# Sheet1.net
KiCad netlist of a schematic drawn in Altium Designer
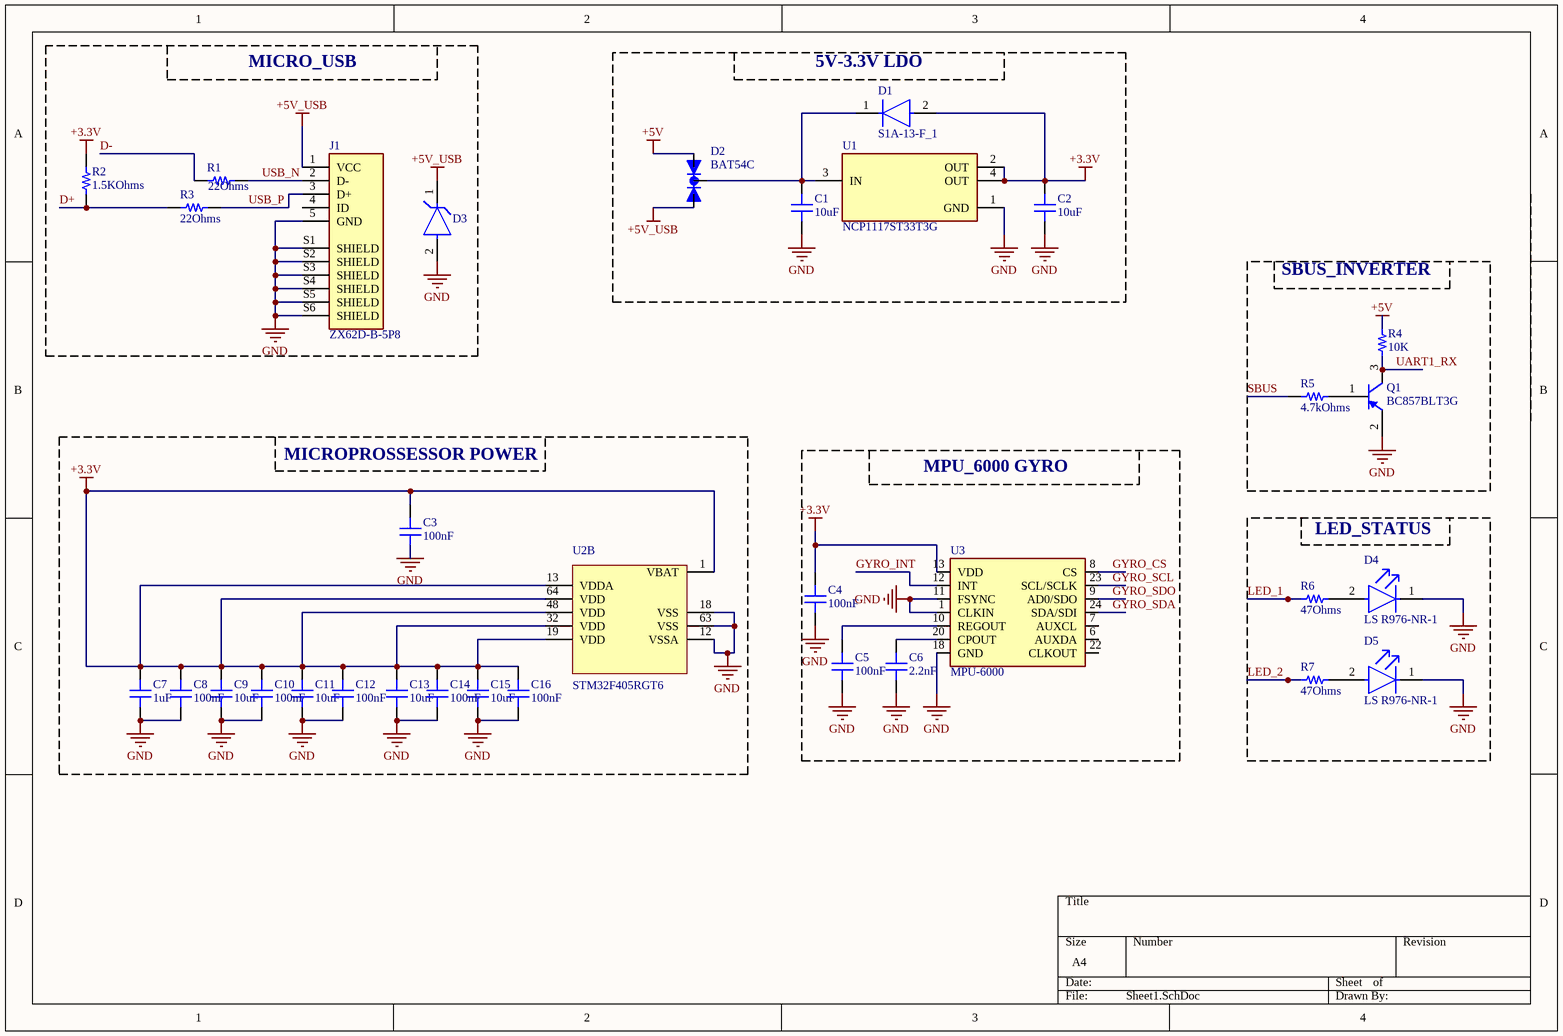
[diagram p0: Sheet1.SchDoc]

(export (version "E")
  (design (tool "Eeschema 10.0.6"))
  (components
    (comp (ref "C1")
      (value "10uF")
      (footprint "CAP-0603")
      (description "10 µF ±20% 16V Ceramic Capacitor X5R 0603 (1608 Metric)")
      (fields
        (field (name "MANUFACTURER") "KEMET")
        (field (name "MANUFACTURER PART NUMBER") "C0603C104K5RAC7411")
      )
      (libsource (lib "Schlib1") (part "CC0603MRX5R7BB106"))
    )
    (comp (ref "C2")
      (value "10uF")
      (footprint "CAP-0603")
      (description "10 µF ±20% 16V Ceramic Capacitor X5R 0603 (1608 Metric)")
      (fields
        (field (name "MANUFACTURER") "KEMET")
        (field (name "MANUFACTURER PART NUMBER") "C0603C104K5RAC7411")
      )
      (libsource (lib "Schlib1") (part "CC0603MRX5R7BB106"))
    )
    (comp (ref "C3")
      (value "100nF")
      (footprint "CAP-0603")
      (description "Cap Ceramic 0.1uF 50V X7R 10% SMD 0603 125°C Paper T/R 100nF")
      (fields
        (field (name "MANUFACTURER") "KEMET")
        (field (name "MANUFACTURER PART NUMBER") "C0603C104K5RAC7411")
      )
      (libsource (lib "Schlib1") (part "C0603C104K5RAC7411"))
    )
    (comp (ref "C4")
      (value "100nF")
      (footprint "CAP-0603")
      (description "Cap Ceramic 0.1uF 50V X7R 10% SMD 0603 125°C Paper T/R 100nF")
      (fields
        (field (name "MANUFACTURER") "KEMET")
        (field (name "MANUFACTURER PART NUMBER") "C0603C104K5RAC7411")
      )
      (libsource (lib "Schlib1") (part "C0603C104K5RAC7411"))
    )
    (comp (ref "C5")
      (value "100nF")
      (footprint "CAP-0603")
      (description "Cap Ceramic 0.1uF 50V X7R 10% SMD 0603 125°C Paper T/R 100nF")
      (fields
        (field (name "MANUFACTURER") "KEMET")
        (field (name "MANUFACTURER PART NUMBER") "C0603C104K5RAC7411")
      )
      (libsource (lib "Schlib1") (part "C0603C104K5RAC7411"))
    )
    (comp (ref "C6")
      (value "2.2nF")
      (footprint "CAP-0603")
      (description "2200 pF ±10% 16V Ceramic Capacitor X7R 0603 (1608 Metric) 2.2nF")
      (fields
        (field (name "MANUFACTURER") "KEMET")
        (field (name "MANUFACTURER PART NUMBER") "C0603C104K5RAC7411")
      )
      (libsource (lib "Schlib1") (part "0603YC222KAT2A"))
    )
    (comp (ref "C7")
      (value "1uF")
      (footprint "CAP-0603")
      (description "Cap Ceramic 1uF 16V X5R 20% Pad SMD 0603 85C Automotive T/R")
      (fields
        (field (name "MANUFACTURER") "KEMET")
        (field (name "MANUFACTURER PART NUMBER") "C0603C104K5RAC7411")
      )
      (libsource (lib "Schlib1") (part "CC0603MRX5R7BB105"))
    )
    (comp (ref "C8")
      (value "100nF")
      (footprint "CAP-0603")
      (description "Cap Ceramic 0.1uF 50V X7R 10% SMD 0603 125°C Paper T/R 100nF")
      (fields
        (field (name "MANUFACTURER") "KEMET")
        (field (name "MANUFACTURER PART NUMBER") "C0603C104K5RAC7411")
      )
      (libsource (lib "Schlib1") (part "C0603C104K5RAC7411"))
    )
    (comp (ref "C9")
      (value "10uF")
      (footprint "CAP-0603")
      (description "10 µF ±20% 16V Ceramic Capacitor X5R 0603 (1608 Metric)")
      (fields
        (field (name "MANUFACTURER") "KEMET")
        (field (name "MANUFACTURER PART NUMBER") "C0603C104K5RAC7411")
      )
      (libsource (lib "Schlib1") (part "CC0603MRX5R7BB106"))
    )
    (comp (ref "C10")
      (value "100nF")
      (footprint "CAP-0603")
      (description "Cap Ceramic 0.1uF 50V X7R 10% SMD 0603 125°C Paper T/R 100nF")
      (fields
        (field (name "MANUFACTURER") "KEMET")
        (field (name "MANUFACTURER PART NUMBER") "C0603C104K5RAC7411")
      )
      (libsource (lib "Schlib1") (part "C0603C104K5RAC7411"))
    )
    (comp (ref "C11")
      (value "10uF")
      (footprint "CAP-0603")
      (description "10 µF ±20% 16V Ceramic Capacitor X5R 0603 (1608 Metric)")
      (fields
        (field (name "MANUFACTURER") "KEMET")
        (field (name "MANUFACTURER PART NUMBER") "C0603C104K5RAC7411")
      )
      (libsource (lib "Schlib1") (part "CC0603MRX5R7BB106"))
    )
    (comp (ref "C12")
      (value "100nF")
      (footprint "CAP-0603")
      (description "Cap Ceramic 0.1uF 50V X7R 10% SMD 0603 125°C Paper T/R 100nF")
      (fields
        (field (name "MANUFACTURER") "KEMET")
        (field (name "MANUFACTURER PART NUMBER") "C0603C104K5RAC7411")
      )
      (libsource (lib "Schlib1") (part "C0603C104K5RAC7411"))
    )
    (comp (ref "C13")
      (value "10uF")
      (footprint "CAP-0603")
      (description "10 µF ±20% 16V Ceramic Capacitor X5R 0603 (1608 Metric)")
      (fields
        (field (name "MANUFACTURER") "KEMET")
        (field (name "MANUFACTURER PART NUMBER") "C0603C104K5RAC7411")
      )
      (libsource (lib "Schlib1") (part "CC0603MRX5R7BB106"))
    )
    (comp (ref "C14")
      (value "100nF")
      (footprint "CAP-0603")
      (description "Cap Ceramic 0.1uF 50V X7R 10% SMD 0603 125°C Paper T/R 100nF")
      (fields
        (field (name "MANUFACTURER") "KEMET")
        (field (name "MANUFACTURER PART NUMBER") "C0603C104K5RAC7411")
      )
      (libsource (lib "Schlib1") (part "C0603C104K5RAC7411"))
    )
    (comp (ref "C15")
      (value "10uF")
      (footprint "CAP-0603")
      (description "10 µF ±20% 16V Ceramic Capacitor X5R 0603 (1608 Metric)")
      (fields
        (field (name "MANUFACTURER") "KEMET")
        (field (name "MANUFACTURER PART NUMBER") "C0603C104K5RAC7411")
      )
      (libsource (lib "Schlib1") (part "CC0603MRX5R7BB106"))
    )
    (comp (ref "C16")
      (value "100nF")
      (footprint "CAP-0603")
      (description "Cap Ceramic 0.1uF 50V X7R 10% SMD 0603 125°C Paper T/R 100nF")
      (fields
        (field (name "MANUFACTURER") "KEMET")
        (field (name "MANUFACTURER PART NUMBER") "C0603C104K5RAC7411")
      )
      (libsource (lib "Schlib1") (part "C0603C104K5RAC7411"))
    )
    (comp (ref "D1")
      (value "S1A-13-F_1")
      (footprint "S1A-13-F")
      (description "VR=50V IF=1A 10pF Trr=3us")
      (fields (field (name "MANUFACTURER") "Diodes") (field (name "MANUFACTURER PART NUMBER") "S1A-13-F"))
      (libsource (lib "Schlib1") (part "S1A-13-F_1"))
    )
    (comp (ref "D2")
      (value "BAT54C")
      (footprint "SOT23-3")
      (description "Diode Array 1 Pair Common Cathode Schottky 30V 200mA Surface Mount TO-236-3, SC-59, SOT-23-3")
      (fields (field (name "MF") "ON Semiconductor"))
      (libsource (lib "Schlib1") (part "BAT54C"))
    )
    (comp (ref "D3")
      (value "ESDA7P60-1U1M")
      (footprint "TVS-1610")
      (description "ESDA Series 6.4 V 700 W SMT Uni-Directional TVS Diode - 1610")
      (fields (field (name "MANUFACTURER") "STMicroelectronics"))
      (libsource (lib "Schlib1") (part "ESDA7P60-1U1M"))
    )
    (comp (ref "D4")
      (value "LS R976-NR-1")
      (footprint "LS R976-NR-1")
      (description "Led SMT Red 0805 Tape")
      (fields
        (field (name "MANUFACTURER") "Osram Opto")
        (field (name "MANUFACTURER PART NUMBER") "LSR976-NR-1")
      )
      (libsource (lib "Schlib1") (part "LS R976-NR-1"))
    )
    (comp (ref "D5")
      (value "LS R976-NR-1")
      (footprint "LS R976-NR-1")
      (description "Led SMT Red 0805 Tape")
      (fields
        (field (name "MANUFACTURER") "Osram Opto")
        (field (name "MANUFACTURER PART NUMBER") "LSR976-NR-1")
      )
      (libsource (lib "Schlib1") (part "LS R976-NR-1"))
    )
    (comp (ref "J1")
      (value "ZX62D-B-5P8")
      (footprint "HRS_ZX62D-B-5P8")
      (description "Conn Micro USB 2.0 Type B RCP 5 POS 0.65mm Solder RA SMD 5 Terminal 1 Port Embossed T/R")
      (fields (field (name "MF") "Hirose"))
      (libsource (lib "Schlib1") (part "ZX62D-B-5P8"))
    )
    (comp (ref "Q1")
      (value "BC857BLT3G")
      (footprint "SOT23-3")
      (description "General Purpose Transistor, PNP Silicon, 3-Pin SOT-23, Pb-Free, Tape and Reel")
      (fields (field (name "MANUFACTURER") "On Semiconductor"))
      (libsource (lib "Schlib1") (part "BC857BLT3G"))
    )
    (comp (ref "R1")
      (value "22Ohms")
      (footprint "RES-0603")
      (description "22 Ohms ±5% 0.1W, 1/10W Chip Resistor 0603 (1608 Metric) Moisture Resistant Thick Film")
      (fields
        (field (name "MANUFACTURER") "Yageo")
        (field (name "MANUFACTURER PART NUMBER") "RC0402JR-071K2L")
      )
      (libsource (lib "Schlib1") (part "RC0603JR-0722RL"))
    )
    (comp (ref "R2")
      (value "1.5KOhms")
      (footprint "RES-0603")
      (description "1500Ω ± 1.00% 0.1W ± 100ppm/℃ 0603")
      (fields
        (field (name "MANUFACTURER") "Yageo")
        (field (name "MANUFACTURER PART NUMBER") "RC0603FR-0710KL")
      )
      (libsource (lib "Schlib1") (part "RC0603FR-071K5L"))
    )
    (comp (ref "R3")
      (value "22Ohms")
      (footprint "RES-0603")
      (description "22 Ohms ±5% 0.1W, 1/10W Chip Resistor 0603 (1608 Metric) Moisture Resistant Thick Film")
      (fields
        (field (name "MANUFACTURER") "Yageo")
        (field (name "MANUFACTURER PART NUMBER") "RC0402JR-071K2L")
      )
      (libsource (lib "Schlib1") (part "RC0603JR-0722RL"))
    )
    (comp (ref "R4")
      (value "10K")
      (footprint "RES-0603")
      (description "10 kOhms ±1% 0.1W, 1/10W Chip Resistor 0603 (1608 Metric) Moisture Resistant Thick Film")
      (fields
        (field (name "MANUFACTURER") "Yageo")
        (field (name "MANUFACTURER PART NUMBER") "RC0603FR-0710KL")
      )
      (libsource (lib "Schlib1") (part "RC0603FR-0710KL"))
    )
    (comp (ref "R5")
      (value "4.7kOhms")
      (footprint "RES-0603")
      (description "4.7 kOhms ±1% 0.1W, 1/10W Chip Resistor 0603 (1608 Metric) Moisture Resistant Thick Film")
      (fields
        (field (name "MANUFACTURER") "Yageo")
        (field (name "MANUFACTURER PART NUMBER") "RC0603FR-0710KL")
      )
      (libsource (lib "Schlib1") (part "RC0603FR-074K7L"))
    )
    (comp (ref "R6")
      (value "47Ohms")
      (footprint "RES-0603")
      (description "47Ω ± 5.00% 0.1W ± 100ppm/℃ 0603")
      (fields
        (field (name "MANUFACTURER") "Yageo")
        (field (name "MANUFACTURER PART NUMBER") "RC0402JR-071K2L")
      )
      (libsource (lib "Schlib1") (part "RC0603JR-0722RL_1"))
    )
    (comp (ref "R7")
      (value "47Ohms")
      (footprint "RES-0603")
      (description "47Ω ± 5.00% 0.1W ± 100ppm/℃ 0603")
      (fields
        (field (name "MANUFACTURER") "Yageo")
        (field (name "MANUFACTURER PART NUMBER") "RC0402JR-071K2L")
      )
      (libsource (lib "Schlib1") (part "RC0603JR-0722RL_1"))
    )
    (comp (ref "U1")
      (value "NCP1117ST33T3G")
      (footprint "SOT-223-4")
      (description "Linear Voltage Regulator IC 1 Output 1A SOT-223")
      (fields (field (name "MF") "ON Semiconductor"))
      (libsource (lib "Schlib1") (part "NCP1117ST33T3G"))
    )
    (comp (ref "U2")
      (value "STM32F405RGT6")
      (footprint "STMicroelectronics_LQFP64-5W_MFG")
      (description "ARMÂ® CortexÂ®-M4 STM32F4 Microcontroller IC 32-Bit 168MHz 1MB _1M x 8_ FLASH 64-LQFP _10x10_")
      (fields (field (name "MF") "STMicroelectronics") (field (name "DIGI-KEY_PART_NUMBER") "497-11767-ND"))
      (libsource (lib "Schlib1") (part "STM32F405RGT6"))
    )
    (comp (ref "U3")
      (value "MPU-6000")
      (footprint "QFN-24-EP")
      (description "Accelerometer, Gyroscope, 6 Axis Sensor I2C, SPI Output")
      (fields (field (name "MF") "TDK InvenSense"))
      (libsource (lib "Schlib1") (part "MPU-6000"))
    )
  )
  (nets
    (net (code "1") (name "+3.3V") (class "Default")
      (node (ref "C10") (pin "2") (pinfunction "2_2") (pintype "passive"))
      (node (ref "C11") (pin "2") (pinfunction "2_2") (pintype "passive"))
      (node (ref "C12") (pin "2") (pinfunction "2_2") (pintype "passive"))
      (node (ref "C13") (pin "2") (pinfunction "2_2") (pintype "passive"))
      (node (ref "C14") (pin "2") (pinfunction "2_2") (pintype "passive"))
      (node (ref "C15") (pin "2") (pinfunction "2_2") (pintype "passive"))
      (node (ref "C16") (pin "2") (pinfunction "2_2") (pintype "passive"))
      (node (ref "C2") (pin "2") (pinfunction "2_2") (pintype "passive"))
      (node (ref "C3") (pin "2") (pinfunction "2_2") (pintype "passive"))
      (node (ref "C4") (pin "2") (pinfunction "2_2") (pintype "passive"))
      (node (ref "C7") (pin "2") (pinfunction "2_2") (pintype "passive"))
      (node (ref "C8") (pin "2") (pinfunction "2_2") (pintype "passive"))
      (node (ref "C9") (pin "2") (pinfunction "2_2") (pintype "passive"))
      (node (ref "D1") (pin "2") (pinfunction "A_2") (pintype "passive"))
      (node (ref "R2") (pin "2") (pinfunction "2_2") (pintype "passive"))
      (node (ref "U1") (pin "2") (pinfunction "OUT_2") (pintype "passive"))
      (node (ref "U1") (pin "4") (pinfunction "OUT_4") (pintype "passive"))
      (node (ref "U2") (pin "1") (pinfunction "VBAT_1") (pintype "passive"))
      (node (ref "U2") (pin "13") (pinfunction "VDDA_13") (pintype "passive"))
      (node (ref "U2") (pin "19") (pinfunction "VDD_19") (pintype "passive"))
      (node (ref "U2") (pin "32") (pinfunction "VDD_32") (pintype "passive"))
      (node (ref "U2") (pin "48") (pinfunction "VDD_48") (pintype "passive"))
      (node (ref "U2") (pin "64") (pinfunction "VDD_64") (pintype "passive"))
      (node (ref "U3") (pin "13") (pinfunction "VDD_13") (pintype "passive"))
    )
    (net (code "2") (name "+5V") (class "Default")
      (node (ref "D2") (pin "1") (pinfunction "A1_1") (pintype "passive"))
      (node (ref "R4") (pin "2") (pinfunction "2_2") (pintype "passive"))
    )
    (net (code "3") (name "+5V_USB") (class "Default")
      (node (ref "D2") (pin "2") (pinfunction "A2_2") (pintype "passive"))
      (node (ref "D3") (pin "1") (pinfunction "C_1") (pintype "passive"))
      (node (ref "J1") (pin "1") (pinfunction "VCC_1") (pintype "passive"))
    )
    (net (code "4") (name "/D+") (class "Default")
      (node (ref "R2") (pin "1") (pinfunction "1_1") (pintype "passive"))
      (node (ref "R3") (pin "1") (pinfunction "1_1") (pintype "passive"))
    )
    (net (code "5") (name "/D-") (class "Default")
      (node (ref "R1") (pin "1") (pinfunction "1_1") (pintype "passive"))
    )
    (net (code "6") (name "/GYRO_CS") (class "Default")
      (node (ref "U3") (pin "8") (pinfunction "CS_8") (pintype "passive"))
    )
    (net (code "7") (name "/GYRO_INT") (class "Default")
      (node (ref "U3") (pin "12") (pinfunction "INT_12") (pintype "passive"))
    )
    (net (code "8") (name "/GYRO_SCL") (class "Default")
      (node (ref "U3") (pin "23") (pinfunction "SCL/SCLK_23") (pintype "passive"))
    )
    (net (code "9") (name "/GYRO_SDA") (class "Default")
      (node (ref "U3") (pin "24") (pinfunction "SDA/SDI_24") (pintype "passive"))
    )
    (net (code "10") (name "/GYRO_SDO") (class "Default")
      (node (ref "U3") (pin "9") (pinfunction "AD0/SDO_9") (pintype "passive"))
    )
    (net (code "11") (name "/LED_1") (class "Default")
      (node (ref "R6") (pin "2") (pinfunction "2_2") (pintype "passive"))
    )
    (net (code "12") (name "/LED_2") (class "Default")
      (node (ref "R7") (pin "2") (pinfunction "2_2") (pintype "passive"))
    )
    (net (code "13") (name "/SBUS") (class "Default")
      (node (ref "R5") (pin "1") (pinfunction "1_1") (pintype "passive"))
    )
    (net (code "14") (name "/UART1_RX") (class "Default")
      (node (ref "Q1") (pin "3") (pinfunction "C_3") (pintype "passive"))
      (node (ref "R4") (pin "1") (pinfunction "1_1") (pintype "passive"))
    )
    (net (code "15") (name "/USB_N") (class "Default")
      (node (ref "J1") (pin "2") (pinfunction "D-_2") (pintype "passive"))
      (node (ref "R1") (pin "2") (pinfunction "2_2") (pintype "passive"))
    )
    (net (code "16") (name "/USB_P") (class "Default")
      (node (ref "J1") (pin "3") (pinfunction "D+_3") (pintype "passive"))
      (node (ref "R3") (pin "2") (pinfunction "2_2") (pintype "passive"))
    )
    (net (code "17") (name "GND") (class "Default")
      (node (ref "C1") (pin "1") (pinfunction "1_1") (pintype "passive"))
      (node (ref "C10") (pin "1") (pinfunction "1_1") (pintype "passive"))
      (node (ref "C11") (pin "1") (pinfunction "1_1") (pintype "passive"))
      (node (ref "C12") (pin "1") (pinfunction "1_1") (pintype "passive"))
      (node (ref "C13") (pin "1") (pinfunction "1_1") (pintype "passive"))
      (node (ref "C14") (pin "1") (pinfunction "1_1") (pintype "passive"))
      (node (ref "C15") (pin "1") (pinfunction "1_1") (pintype "passive"))
      (node (ref "C16") (pin "1") (pinfunction "1_1") (pintype "passive"))
      (node (ref "C2") (pin "1") (pinfunction "1_1") (pintype "passive"))
      (node (ref "C3") (pin "1") (pinfunction "1_1") (pintype "passive"))
      (node (ref "C4") (pin "1") (pinfunction "1_1") (pintype "passive"))
      (node (ref "C5") (pin "2") (pinfunction "2_2") (pintype "passive"))
      (node (ref "C6") (pin "1") (pinfunction "1_1") (pintype "passive"))
      (node (ref "C7") (pin "1") (pinfunction "1_1") (pintype "passive"))
      (node (ref "C8") (pin "1") (pinfunction "1_1") (pintype "passive"))
      (node (ref "C9") (pin "1") (pinfunction "1_1") (pintype "passive"))
      (node (ref "D3") (pin "2") (pinfunction "A_2") (pintype "passive"))
      (node (ref "D4") (pin "1") (pinfunction "C_1") (pintype "passive"))
      (node (ref "D5") (pin "1") (pinfunction "C_1") (pintype "passive"))
      (node (ref "J1") (pin "5") (pinfunction "GND_5") (pintype "passive"))
      (node (ref "J1") (pin "S1") (pinfunction "SHIELD_S1") (pintype "passive"))
      (node (ref "J1") (pin "S2") (pinfunction "SHIELD_S2") (pintype "passive"))
      (node (ref "J1") (pin "S3") (pinfunction "SHIELD_S3") (pintype "passive"))
      (node (ref "J1") (pin "S4") (pinfunction "SHIELD_S4") (pintype "passive"))
      (node (ref "J1") (pin "S5") (pinfunction "SHIELD_S5") (pintype "passive"))
      (node (ref "J1") (pin "S6") (pinfunction "SHIELD_S6") (pintype "passive"))
      (node (ref "Q1") (pin "2") (pinfunction "E_2") (pintype "passive"))
      (node (ref "U1") (pin "1") (pinfunction "GND_1") (pintype "passive"))
      (node (ref "U2") (pin "12") (pinfunction "VSSA_12") (pintype "passive"))
      (node (ref "U2") (pin "18") (pinfunction "VSS_18") (pintype "passive"))
      (node (ref "U2") (pin "63") (pinfunction "VSS_63") (pintype "passive"))
      (node (ref "U3") (pin "1") (pinfunction "CLKIN_1") (pintype "passive"))
      (node (ref "U3") (pin "11") (pinfunction "FSYNC_11") (pintype "passive"))
      (node (ref "U3") (pin "18") (pinfunction "GND_18") (pintype "passive"))
    )
    (net (code "18") (name "Net-(D1-C)") (class "Default")
      (node (ref "C1") (pin "2") (pinfunction "2_2") (pintype "passive"))
      (node (ref "D1") (pin "1") (pinfunction "C_1") (pintype "passive"))
      (node (ref "D2") (pin "3") (pinfunction "C_3") (pintype "passive"))
      (node (ref "U1") (pin "3") (pinfunction "IN_3") (pintype "passive"))
    )
    (net (code "19") (name "Net-(D4-A)") (class "Default")
      (node (ref "D4") (pin "2") (pinfunction "A_2") (pintype "passive"))
      (node (ref "R6") (pin "1") (pinfunction "1_1") (pintype "passive"))
    )
    (net (code "20") (name "Net-(D5-A)") (class "Default")
      (node (ref "D5") (pin "2") (pinfunction "A_2") (pintype "passive"))
      (node (ref "R7") (pin "1") (pinfunction "1_1") (pintype "passive"))
    )
    (net (code "21") (name "Net-(Q1-B)") (class "Default")
      (node (ref "Q1") (pin "1") (pinfunction "B_1") (pintype "passive"))
      (node (ref "R5") (pin "2") (pinfunction "2_2") (pintype "passive"))
    )
    (net (code "22") (name "Net-(U3-CPOUT)") (class "Default")
      (node (ref "C6") (pin "2") (pinfunction "2_2") (pintype "passive"))
      (node (ref "U3") (pin "20") (pinfunction "CPOUT_20") (pintype "passive"))
    )
    (net (code "23") (name "Net-(U3-REGOUT)") (class "Default")
      (node (ref "C5") (pin "1") (pinfunction "1_1") (pintype "passive"))
      (node (ref "U3") (pin "10") (pinfunction "REGOUT_10") (pintype "passive"))
    )
    (net (code "24") (name "unconnected-(J1-ID-Pad4)") (class "Default")
      (node (ref "J1") (pin "4") (pinfunction "ID_4") (pintype "passive"))
    )
    (net (code "25") (name "unconnected-(U3-AUXCL-Pad7)") (class "Default")
      (node (ref "U3") (pin "7") (pinfunction "AUXCL_7") (pintype "passive"))
    )
    (net (code "26") (name "unconnected-(U3-AUXDA-Pad6)") (class "Default")
      (node (ref "U3") (pin "6") (pinfunction "AUXDA_6") (pintype "passive"))
    )
    (net (code "27") (name "unconnected-(U3-CLKOUT-Pad22)") (class "Default")
      (node (ref "U3") (pin "22") (pinfunction "CLKOUT_22") (pintype "passive"))
    )
  )
)
